# IO_TOP_BOARD.net
KiCad netlist of a schematic drawn in EAGLE
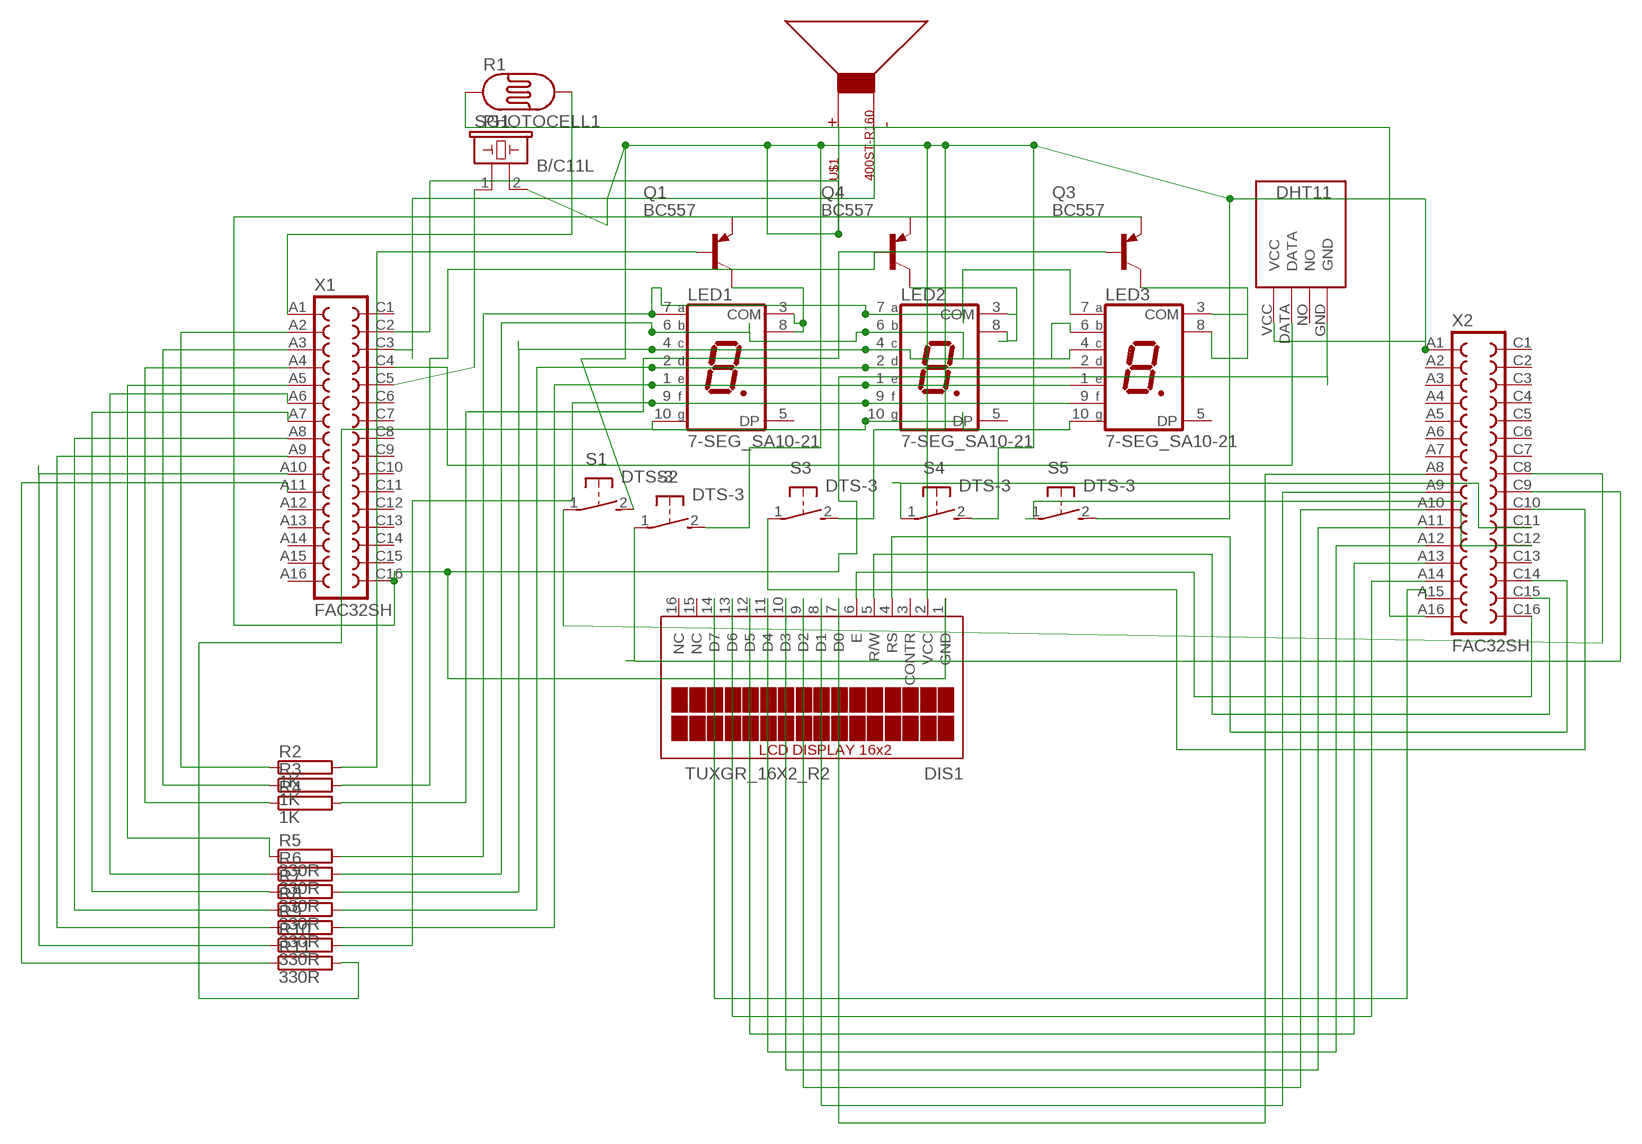
[diagram p0: schematic, sheet 1]

(export (version "E")
  (design (tool "Eeschema 10.0.6"))
  (components
    (comp (ref "DIS1")
      (value "TUXGR_16X2_R2")
      (footprint "eagle-import:TUXGR_16X2_R2")
      (libsource (lib "eagle-import") (part "TUXGR_16X2_R2"))
    )
    (comp (ref "LED1")
      (value "7-SEG_SA10-21")
      (footprint "eagle-import:SA10-21")
      (libsource (lib "eagle-import") (part "7-SEG_SA10-21"))
    )
    (comp (ref "LED2")
      (value "7-SEG_SA10-21")
      (footprint "eagle-import:SA10-21")
      (libsource (lib "eagle-import") (part "7-SEG_SA10-21"))
    )
    (comp (ref "LED3")
      (value "7-SEG_SA10-21")
      (footprint "eagle-import:SA10-21")
      (libsource (lib "eagle-import") (part "7-SEG_SA10-21"))
    )
    (comp (ref "Q1")
      (value "BC557")
      (footprint "eagle-import:TO92")
      (libsource (lib "eagle-import") (part "BC557"))
    )
    (comp (ref "Q3")
      (value "BC557")
      (footprint "eagle-import:TO92")
      (libsource (lib "eagle-import") (part "BC557"))
    )
    (comp (ref "Q4")
      (value "BC557")
      (footprint "eagle-import:TO92")
      (libsource (lib "eagle-import") (part "BC557"))
    )
    (comp (ref "R1")
      (value "PHOTOCELL1")
      (footprint "eagle-import:LDR_OFFBOARD")
      (libsource (lib "eagle-import") (part "PHOTOCELL1"))
    )
    (comp (ref "R2")
      (value "1K")
      (footprint "eagle-import:TO-247-2H")
      (libsource (lib "eagle-import") (part "RMG100-H"))
    )
    (comp (ref "R3")
      (value "1K")
      (footprint "eagle-import:TO-247-2H")
      (libsource (lib "eagle-import") (part "RMG100-H"))
    )
    (comp (ref "R4")
      (value "1K")
      (footprint "eagle-import:TO-247-2H")
      (libsource (lib "eagle-import") (part "RMG100-H"))
    )
    (comp (ref "R5")
      (value "330R")
      (footprint "eagle-import:TO-247-2H")
      (libsource (lib "eagle-import") (part "RMG100-H"))
    )
    (comp (ref "R6")
      (value "330R")
      (footprint "eagle-import:TO-247-2H")
      (libsource (lib "eagle-import") (part "RMG100-H"))
    )
    (comp (ref "R7")
      (value "330R")
      (footprint "eagle-import:TO-247-2H")
      (libsource (lib "eagle-import") (part "RMG100-H"))
    )
    (comp (ref "R8")
      (value "330R")
      (footprint "eagle-import:TO-247-2H")
      (libsource (lib "eagle-import") (part "RMG100-H"))
    )
    (comp (ref "R9")
      (value "330R")
      (footprint "eagle-import:TO-247-2H")
      (libsource (lib "eagle-import") (part "RMG100-H"))
    )
    (comp (ref "R10")
      (value "330R")
      (footprint "eagle-import:TO-247-2H")
      (libsource (lib "eagle-import") (part "RMG100-H"))
    )
    (comp (ref "R11")
      (value "330R")
      (footprint "eagle-import:TO-247-2H")
      (libsource (lib "eagle-import") (part "RMG100-H"))
    )
    (comp (ref "S1")
      (value "DTS-3")
      (footprint "eagle-import:DTS-3")
      (libsource (lib "eagle-import") (part "DTS-3"))
    )
    (comp (ref "S2")
      (value "DTS-3")
      (footprint "eagle-import:DTS-3")
      (libsource (lib "eagle-import") (part "DTS-3"))
    )
    (comp (ref "S3")
      (value "DTS-3")
      (footprint "eagle-import:DTS-3")
      (libsource (lib "eagle-import") (part "DTS-3"))
    )
    (comp (ref "S4")
      (value "DTS-3")
      (footprint "eagle-import:DTS-3")
      (libsource (lib "eagle-import") (part "DTS-3"))
    )
    (comp (ref "S5")
      (value "DTS-3")
      (footprint "eagle-import:DTS-3")
      (libsource (lib "eagle-import") (part "DTS-3"))
    )
    (comp (ref "SG1")
      (value "B/C11L")
      (footprint "eagle-import:B_C11L")
      (libsource (lib "eagle-import") (part "B/C11L"))
    )
    (comp (ref "U$1")
      (value "400ST-R160")
      (footprint "eagle-import:400STR160")
      (libsource (lib "eagle-import") (part "400ST-R160"))
    )
    (comp (ref "U$2")
      (value "DHT11")
      (footprint "eagle-import:DHT11")
      (libsource (lib "eagle-import") (part "DHT11"))
    )
    (comp (ref "X1")
      (value "FAC32SH")
      (footprint "eagle-import:FAC32SH")
      (libsource (lib "eagle-import") (part "FAC32SH"))
    )
    (comp (ref "X2")
      (value "FAC32SH")
      (footprint "eagle-import:FAC32SH")
      (libsource (lib "eagle-import") (part "FAC32SH"))
    )
  )
  (nets
    (net (code "1") (name "Net-(DIS1-D0)") (class "Default")
      (node (ref "DIS1") (pin "7") (pinfunction "D0_7") (pintype "input"))
      (node (ref "X2") (pin "A8") (pinfunction "A8_A8") (pintype "passive"))
    )
    (net (code "2") (name "Net-(DIS1-D1)") (class "Default")
      (node (ref "DIS1") (pin "8") (pinfunction "D1_8") (pintype "input"))
      (node (ref "X2") (pin "A9") (pinfunction "A9_A9") (pintype "passive"))
    )
    (net (code "3") (name "Net-(DIS1-D2)") (class "Default")
      (node (ref "DIS1") (pin "9") (pinfunction "D2_9") (pintype "input"))
      (node (ref "X2") (pin "A10") (pinfunction "A10_A10") (pintype "passive"))
    )
    (net (code "4") (name "Net-(DIS1-D3)") (class "Default")
      (node (ref "DIS1") (pin "10") (pinfunction "D3_10") (pintype "input"))
      (node (ref "X2") (pin "A11") (pinfunction "A11_A11") (pintype "passive"))
    )
    (net (code "5") (name "Net-(DIS1-D4)") (class "Default")
      (node (ref "DIS1") (pin "11") (pinfunction "D4_11") (pintype "input"))
      (node (ref "X2") (pin "A12") (pinfunction "A12_A12") (pintype "passive"))
    )
    (net (code "6") (name "Net-(DIS1-D5)") (class "Default")
      (node (ref "DIS1") (pin "12") (pinfunction "D5_12") (pintype "input"))
      (node (ref "X2") (pin "A13") (pinfunction "A13_A13") (pintype "passive"))
    )
    (net (code "7") (name "Net-(DIS1-D6)") (class "Default")
      (node (ref "DIS1") (pin "13") (pinfunction "D6_13") (pintype "input"))
      (node (ref "X2") (pin "A14") (pinfunction "A14_A14") (pintype "passive"))
    )
    (net (code "8") (name "Net-(DIS1-D7)") (class "Default")
      (node (ref "DIS1") (pin "14") (pinfunction "D7_14") (pintype "input"))
      (node (ref "X2") (pin "A15") (pinfunction "A15_A15") (pintype "passive"))
    )
    (net (code "9") (name "Net-(DIS1-E)") (class "Default")
      (node (ref "DIS1") (pin "6") (pinfunction "E_6") (pintype "input"))
      (node (ref "X2") (pin "C16") (pinfunction "C16_C16") (pintype "passive"))
    )
    (net (code "10") (name "Net-(DIS1-GND)") (class "Default")
      (node (ref "DIS1") (pin "1") (pinfunction "GND_1") (pintype "power_in"))
      (node (ref "Q3") (pin "1") (pinfunction "E_1") (pintype "passive"))
      (node (ref "U$2") (pin "GND") (pinfunction "GND_GND") (pintype "bidirectional"))
      (node (ref "X1") (pin "C16") (pinfunction "C16_C16") (pintype "passive"))
    )
    (net (code "11") (name "Net-(DIS1-RS)") (class "Default")
      (node (ref "DIS1") (pin "4") (pinfunction "RS_4") (pintype "input"))
      (node (ref "X2") (pin "C14") (pinfunction "C14_C14") (pintype "passive"))
    )
    (net (code "12") (name "Net-(DIS1-R{slash}W)") (class "Default")
      (node (ref "DIS1") (pin "5") (pinfunction "R/W_5") (pintype "input"))
      (node (ref "X2") (pin "C15") (pinfunction "C15_C15") (pintype "passive"))
    )
    (net (code "13") (name "Net-(DIS1-VCC)") (class "Default")
      (node (ref "DIS1") (pin "2") (pinfunction "VCC_2") (pintype "power_in"))
      (node (ref "S1") (pin "2") (pinfunction "2_2") (pintype "passive"))
      (node (ref "S2") (pin "2") (pinfunction "2_2") (pintype "passive"))
      (node (ref "S3") (pin "2") (pinfunction "2_2") (pintype "passive"))
      (node (ref "S4") (pin "2") (pinfunction "2_2") (pintype "passive"))
      (node (ref "S5") (pin "2") (pinfunction "2_2") (pintype "passive"))
      (node (ref "SG1") (pin "2") (pinfunction "2_2") (pintype "passive"))
      (node (ref "U$1") (pin "P$1") (pinfunction "P$1_P$1") (pintype "bidirectional"))
      (node (ref "U$2") (pin "VCC") (pinfunction "VCC_VCC") (pintype "bidirectional"))
      (node (ref "X1") (pin "C2") (pinfunction "C2_C2") (pintype "passive"))
      (node (ref "X2") (pin "A1") (pinfunction "A1_A1") (pintype "passive"))
    )
    (net (code "14") (name "Net-(LED1-A)") (class "Default")
      (node (ref "LED1") (pin "7") (pinfunction "A_7") (pintype "passive"))
      (node (ref "LED2") (pin "7") (pinfunction "A_7") (pintype "passive"))
      (node (ref "LED3") (pin "7") (pinfunction "A_7") (pintype "passive"))
      (node (ref "R5") (pin "2") (pinfunction "2_2") (pintype "passive"))
    )
    (net (code "15") (name "Net-(LED1-B)") (class "Default")
      (node (ref "LED1") (pin "6") (pinfunction "B_6") (pintype "passive"))
      (node (ref "LED2") (pin "6") (pinfunction "B_6") (pintype "passive"))
      (node (ref "LED3") (pin "6") (pinfunction "B_6") (pintype "passive"))
      (node (ref "R6") (pin "2") (pinfunction "2_2") (pintype "passive"))
    )
    (net (code "16") (name "Net-(LED1-C)") (class "Default")
      (node (ref "LED1") (pin "4") (pinfunction "C_4") (pintype "passive"))
      (node (ref "LED2") (pin "4") (pinfunction "C_4") (pintype "passive"))
      (node (ref "LED3") (pin "4") (pinfunction "C_4") (pintype "passive"))
      (node (ref "R7") (pin "2") (pinfunction "2_2") (pintype "passive"))
    )
    (net (code "17") (name "Net-(LED1-D)") (class "Default")
      (node (ref "LED1") (pin "2") (pinfunction "D_2") (pintype "passive"))
      (node (ref "LED2") (pin "2") (pinfunction "D_2") (pintype "passive"))
      (node (ref "LED3") (pin "2") (pinfunction "D_2") (pintype "passive"))
      (node (ref "R8") (pin "2") (pinfunction "2_2") (pintype "passive"))
    )
    (net (code "18") (name "Net-(LED1-E)") (class "Default")
      (node (ref "LED1") (pin "1") (pinfunction "E_1") (pintype "passive"))
      (node (ref "LED2") (pin "1") (pinfunction "E_1") (pintype "passive"))
      (node (ref "LED3") (pin "1") (pinfunction "E_1") (pintype "passive"))
      (node (ref "R9") (pin "2") (pinfunction "2_2") (pintype "passive"))
    )
    (net (code "19") (name "Net-(LED1-F)") (class "Default")
      (node (ref "LED1") (pin "9") (pinfunction "F_9") (pintype "passive"))
      (node (ref "LED2") (pin "9") (pinfunction "F_9") (pintype "passive"))
      (node (ref "LED3") (pin "9") (pinfunction "F_9") (pintype "passive"))
      (node (ref "R10") (pin "2") (pinfunction "2_2") (pintype "passive"))
    )
    (net (code "20") (name "Net-(LED1-G)") (class "Default")
      (node (ref "LED1") (pin "10") (pinfunction "G_10") (pintype "passive"))
      (node (ref "LED2") (pin "10") (pinfunction "G_10") (pintype "passive"))
      (node (ref "LED3") (pin "10") (pinfunction "G_10") (pintype "passive"))
      (node (ref "R11") (pin "2") (pinfunction "2_2") (pintype "passive"))
    )
    (net (code "21") (name "Net-(Q1-B)") (class "Default")
      (node (ref "Q1") (pin "2") (pinfunction "B_2") (pintype "passive"))
      (node (ref "R2") (pin "2") (pinfunction "2_2") (pintype "passive"))
    )
    (net (code "22") (name "Net-(Q1-C)") (class "Default")
      (node (ref "LED1") (pin "3") (pinfunction "COM_3") (pintype "passive"))
      (node (ref "LED1") (pin "8") (pinfunction "COM_8") (pintype "passive"))
      (node (ref "Q1") (pin "3") (pinfunction "C_3") (pintype "passive"))
    )
    (net (code "23") (name "Net-(Q3-B)") (class "Default")
      (node (ref "Q3") (pin "2") (pinfunction "B_2") (pintype "passive"))
      (node (ref "R4") (pin "2") (pinfunction "2_2") (pintype "passive"))
    )
    (net (code "24") (name "Net-(Q3-C)") (class "Default")
      (node (ref "LED3") (pin "3") (pinfunction "COM_3") (pintype "passive"))
      (node (ref "LED3") (pin "8") (pinfunction "COM_8") (pintype "passive"))
      (node (ref "Q3") (pin "3") (pinfunction "C_3") (pintype "passive"))
    )
    (net (code "25") (name "Net-(Q4-B)") (class "Default")
      (node (ref "Q4") (pin "2") (pinfunction "B_2") (pintype "passive"))
      (node (ref "R3") (pin "2") (pinfunction "2_2") (pintype "passive"))
    )
    (net (code "26") (name "Net-(Q4-C)") (class "Default")
      (node (ref "LED2") (pin "3") (pinfunction "COM_3") (pintype "passive"))
      (node (ref "LED2") (pin "8") (pinfunction "COM_8") (pintype "passive"))
      (node (ref "Q4") (pin "3") (pinfunction "C_3") (pintype "passive"))
    )
    (net (code "27") (name "Net-(R1-P$1)") (class "Default")
      (node (ref "R1") (pin "1") (pinfunction "P$1_1") (pintype "bidirectional"))
      (node (ref "X2") (pin "A16") (pinfunction "A16_A16") (pintype "passive"))
    )
    (net (code "28") (name "Net-(R1-P$2)") (class "Default")
      (node (ref "R1") (pin "2") (pinfunction "P$2_2") (pintype "bidirectional"))
      (node (ref "X1") (pin "A1") (pinfunction "A1_A1") (pintype "passive"))
    )
    (net (code "29") (name "Net-(R2-Pad1)") (class "Default")
      (node (ref "R2") (pin "1") (pinfunction "1_1") (pintype "passive"))
      (node (ref "X1") (pin "A2") (pinfunction "A2_A2") (pintype "passive"))
    )
    (net (code "30") (name "Net-(R3-Pad1)") (class "Default")
      (node (ref "R3") (pin "1") (pinfunction "1_1") (pintype "passive"))
      (node (ref "X1") (pin "A3") (pinfunction "A3_A3") (pintype "passive"))
    )
    (net (code "31") (name "Net-(R4-Pad1)") (class "Default")
      (node (ref "R4") (pin "1") (pinfunction "1_1") (pintype "passive"))
      (node (ref "X1") (pin "A4") (pinfunction "A4_A4") (pintype "passive"))
    )
    (net (code "32") (name "Net-(R5-Pad1)") (class "Default")
      (node (ref "R5") (pin "1") (pinfunction "1_1") (pintype "passive"))
      (node (ref "X1") (pin "A5") (pinfunction "A5_A5") (pintype "passive"))
    )
    (net (code "33") (name "Net-(R6-Pad1)") (class "Default")
      (node (ref "R6") (pin "1") (pinfunction "1_1") (pintype "passive"))
      (node (ref "X1") (pin "A6") (pinfunction "A6_A6") (pintype "passive"))
    )
    (net (code "34") (name "Net-(R7-Pad1)") (class "Default")
      (node (ref "R7") (pin "1") (pinfunction "1_1") (pintype "passive"))
      (node (ref "X1") (pin "A7") (pinfunction "A7_A7") (pintype "passive"))
    )
    (net (code "35") (name "Net-(R8-Pad1)") (class "Default")
      (node (ref "R8") (pin "1") (pinfunction "1_1") (pintype "passive"))
      (node (ref "X1") (pin "A8") (pinfunction "A8_A8") (pintype "passive"))
    )
    (net (code "36") (name "Net-(R9-Pad1)") (class "Default")
      (node (ref "R9") (pin "1") (pinfunction "1_1") (pintype "passive"))
      (node (ref "X1") (pin "A9") (pinfunction "A9_A9") (pintype "passive"))
    )
    (net (code "37") (name "Net-(R10-Pad1)") (class "Default")
      (node (ref "R10") (pin "1") (pinfunction "1_1") (pintype "passive"))
      (node (ref "X1") (pin "A10") (pinfunction "A10_A10") (pintype "passive"))
    )
    (net (code "38") (name "Net-(R11-Pad1)") (class "Default")
      (node (ref "R11") (pin "1") (pinfunction "1_1") (pintype "passive"))
      (node (ref "X1") (pin "A11") (pinfunction "A11_A11") (pintype "passive"))
    )
    (net (code "39") (name "Net-(S1-Pad1)") (class "Default")
      (node (ref "S1") (pin "1") (pinfunction "1_1") (pintype "passive"))
      (node (ref "X2") (pin "C8") (pinfunction "C8_C8") (pintype "passive"))
    )
    (net (code "40") (name "Net-(S2-Pad1)") (class "Default")
      (node (ref "S2") (pin "1") (pinfunction "1_1") (pintype "passive"))
      (node (ref "X2") (pin "C9") (pinfunction "C9_C9") (pintype "passive"))
    )
    (net (code "41") (name "Net-(S3-Pad1)") (class "Default")
      (node (ref "S3") (pin "1") (pinfunction "1_1") (pintype "passive"))
      (node (ref "X2") (pin "C10") (pinfunction "C10_C10") (pintype "passive"))
    )
    (net (code "42") (name "Net-(S4-Pad1)") (class "Default")
      (node (ref "S4") (pin "1") (pinfunction "1_1") (pintype "passive"))
      (node (ref "X2") (pin "C11") (pinfunction "C11_C11") (pintype "passive"))
    )
    (net (code "43") (name "Net-(S5-Pad1)") (class "Default")
      (node (ref "S5") (pin "1") (pinfunction "1_1") (pintype "passive"))
      (node (ref "X2") (pin "C12") (pinfunction "C12_C12") (pintype "passive"))
    )
    (net (code "44") (name "Net-(SG1-Pad1)") (class "Default")
      (node (ref "SG1") (pin "1") (pinfunction "1_1") (pintype "passive"))
      (node (ref "X1") (pin "C5") (pinfunction "C5_C5") (pintype "passive"))
    )
    (net (code "45") (name "Net-(U$1-PadP$2)") (class "Default")
      (node (ref "U$1") (pin "P$2") (pinfunction "P$2_P$2") (pintype "bidirectional"))
      (node (ref "X1") (pin "C3") (pinfunction "C3_C3") (pintype "passive"))
    )
    (net (code "46") (name "Net-(U$2-PadDATA)") (class "Default")
      (node (ref "U$2") (pin "DATA") (pinfunction "DATA_DATA") (pintype "bidirectional"))
      (node (ref "X1") (pin "C4") (pinfunction "C4_C4") (pintype "passive"))
    )
    (net (code "47") (name "unconnected-(DIS1-CONTR-Pad3)") (class "Default")
      (node (ref "DIS1") (pin "3") (pinfunction "CONTR_3") (pintype "input"))
    )
    (net (code "48") (name "unconnected-(DIS1-NC-Pad15)") (class "Default")
      (node (ref "DIS1") (pin "15") (pinfunction "NC_15") (pintype "no_connect"))
    )
    (net (code "49") (name "unconnected-(DIS1-NC-Pad16)") (class "Default")
      (node (ref "DIS1") (pin "16") (pinfunction "NC_16") (pintype "no_connect"))
    )
    (net (code "50") (name "unconnected-(LED1-DP-Pad5)") (class "Default")
      (node (ref "LED1") (pin "5") (pinfunction "DP_5") (pintype "passive"))
    )
    (net (code "51") (name "unconnected-(LED2-DP-Pad5)") (class "Default")
      (node (ref "LED2") (pin "5") (pinfunction "DP_5") (pintype "passive"))
    )
    (net (code "52") (name "unconnected-(LED3-DP-Pad5)") (class "Default")
      (node (ref "LED3") (pin "5") (pinfunction "DP_5") (pintype "passive"))
    )
    (net (code "53") (name "unconnected-(Q1-E-Pad1)") (class "Default")
      (node (ref "Q1") (pin "1") (pinfunction "E_1") (pintype "passive"))
    )
    (net (code "54") (name "unconnected-(Q4-E-Pad1)") (class "Default")
      (node (ref "Q4") (pin "1") (pinfunction "E_1") (pintype "passive"))
    )
    (net (code "55") (name "unconnected-(U$2-PadNO)") (class "Default")
      (node (ref "U$2") (pin "NO") (pinfunction "NO_NO") (pintype "bidirectional"))
    )
    (net (code "56") (name "unconnected-(X1-PadA12)") (class "Default")
      (node (ref "X1") (pin "A12") (pinfunction "A12_A12") (pintype "passive"))
    )
    (net (code "57") (name "unconnected-(X1-PadA13)") (class "Default")
      (node (ref "X1") (pin "A13") (pinfunction "A13_A13") (pintype "passive"))
    )
    (net (code "58") (name "unconnected-(X1-PadA14)") (class "Default")
      (node (ref "X1") (pin "A14") (pinfunction "A14_A14") (pintype "passive"))
    )
    (net (code "59") (name "unconnected-(X1-PadA15)") (class "Default")
      (node (ref "X1") (pin "A15") (pinfunction "A15_A15") (pintype "passive"))
    )
    (net (code "60") (name "unconnected-(X1-PadA16)") (class "Default")
      (node (ref "X1") (pin "A16") (pinfunction "A16_A16") (pintype "passive"))
    )
    (net (code "61") (name "unconnected-(X1-PadC1)") (class "Default")
      (node (ref "X1") (pin "C1") (pinfunction "C1_C1") (pintype "passive"))
    )
    (net (code "62") (name "unconnected-(X1-PadC6)") (class "Default")
      (node (ref "X1") (pin "C6") (pinfunction "C6_C6") (pintype "passive"))
    )
    (net (code "63") (name "unconnected-(X1-PadC7)") (class "Default")
      (node (ref "X1") (pin "C7") (pinfunction "C7_C7") (pintype "passive"))
    )
    (net (code "64") (name "unconnected-(X1-PadC8)") (class "Default")
      (node (ref "X1") (pin "C8") (pinfunction "C8_C8") (pintype "passive"))
    )
    (net (code "65") (name "unconnected-(X1-PadC9)") (class "Default")
      (node (ref "X1") (pin "C9") (pinfunction "C9_C9") (pintype "passive"))
    )
    (net (code "66") (name "unconnected-(X1-PadC10)") (class "Default")
      (node (ref "X1") (pin "C10") (pinfunction "C10_C10") (pintype "passive"))
    )
    (net (code "67") (name "unconnected-(X1-PadC11)") (class "Default")
      (node (ref "X1") (pin "C11") (pinfunction "C11_C11") (pintype "passive"))
    )
    (net (code "68") (name "unconnected-(X1-PadC12)") (class "Default")
      (node (ref "X1") (pin "C12") (pinfunction "C12_C12") (pintype "passive"))
    )
    (net (code "69") (name "unconnected-(X1-PadC13)") (class "Default")
      (node (ref "X1") (pin "C13") (pinfunction "C13_C13") (pintype "passive"))
    )
    (net (code "70") (name "unconnected-(X1-PadC14)") (class "Default")
      (node (ref "X1") (pin "C14") (pinfunction "C14_C14") (pintype "passive"))
    )
    (net (code "71") (name "unconnected-(X1-PadC15)") (class "Default")
      (node (ref "X1") (pin "C15") (pinfunction "C15_C15") (pintype "passive"))
    )
    (net (code "72") (name "unconnected-(X2-PadA2)") (class "Default")
      (node (ref "X2") (pin "A2") (pinfunction "A2_A2") (pintype "passive"))
    )
    (net (code "73") (name "unconnected-(X2-PadA3)") (class "Default")
      (node (ref "X2") (pin "A3") (pinfunction "A3_A3") (pintype "passive"))
    )
    (net (code "74") (name "unconnected-(X2-PadA4)") (class "Default")
      (node (ref "X2") (pin "A4") (pinfunction "A4_A4") (pintype "passive"))
    )
    (net (code "75") (name "unconnected-(X2-PadA5)") (class "Default")
      (node (ref "X2") (pin "A5") (pinfunction "A5_A5") (pintype "passive"))
    )
    (net (code "76") (name "unconnected-(X2-PadA6)") (class "Default")
      (node (ref "X2") (pin "A6") (pinfunction "A6_A6") (pintype "passive"))
    )
    (net (code "77") (name "unconnected-(X2-PadA7)") (class "Default")
      (node (ref "X2") (pin "A7") (pinfunction "A7_A7") (pintype "passive"))
    )
    (net (code "78") (name "unconnected-(X2-PadC1)") (class "Default")
      (node (ref "X2") (pin "C1") (pinfunction "C1_C1") (pintype "passive"))
    )
    (net (code "79") (name "unconnected-(X2-PadC2)") (class "Default")
      (node (ref "X2") (pin "C2") (pinfunction "C2_C2") (pintype "passive"))
    )
    (net (code "80") (name "unconnected-(X2-PadC3)") (class "Default")
      (node (ref "X2") (pin "C3") (pinfunction "C3_C3") (pintype "passive"))
    )
    (net (code "81") (name "unconnected-(X2-PadC4)") (class "Default")
      (node (ref "X2") (pin "C4") (pinfunction "C4_C4") (pintype "passive"))
    )
    (net (code "82") (name "unconnected-(X2-PadC5)") (class "Default")
      (node (ref "X2") (pin "C5") (pinfunction "C5_C5") (pintype "passive"))
    )
    (net (code "83") (name "unconnected-(X2-PadC6)") (class "Default")
      (node (ref "X2") (pin "C6") (pinfunction "C6_C6") (pintype "passive"))
    )
    (net (code "84") (name "unconnected-(X2-PadC7)") (class "Default")
      (node (ref "X2") (pin "C7") (pinfunction "C7_C7") (pintype "passive"))
    )
    (net (code "85") (name "unconnected-(X2-PadC13)") (class "Default")
      (node (ref "X2") (pin "C13") (pinfunction "C13_C13") (pintype "passive"))
    )
  )
)
